# TinyCan.net
KiCad netlist of a schematic drawn in EAGLE
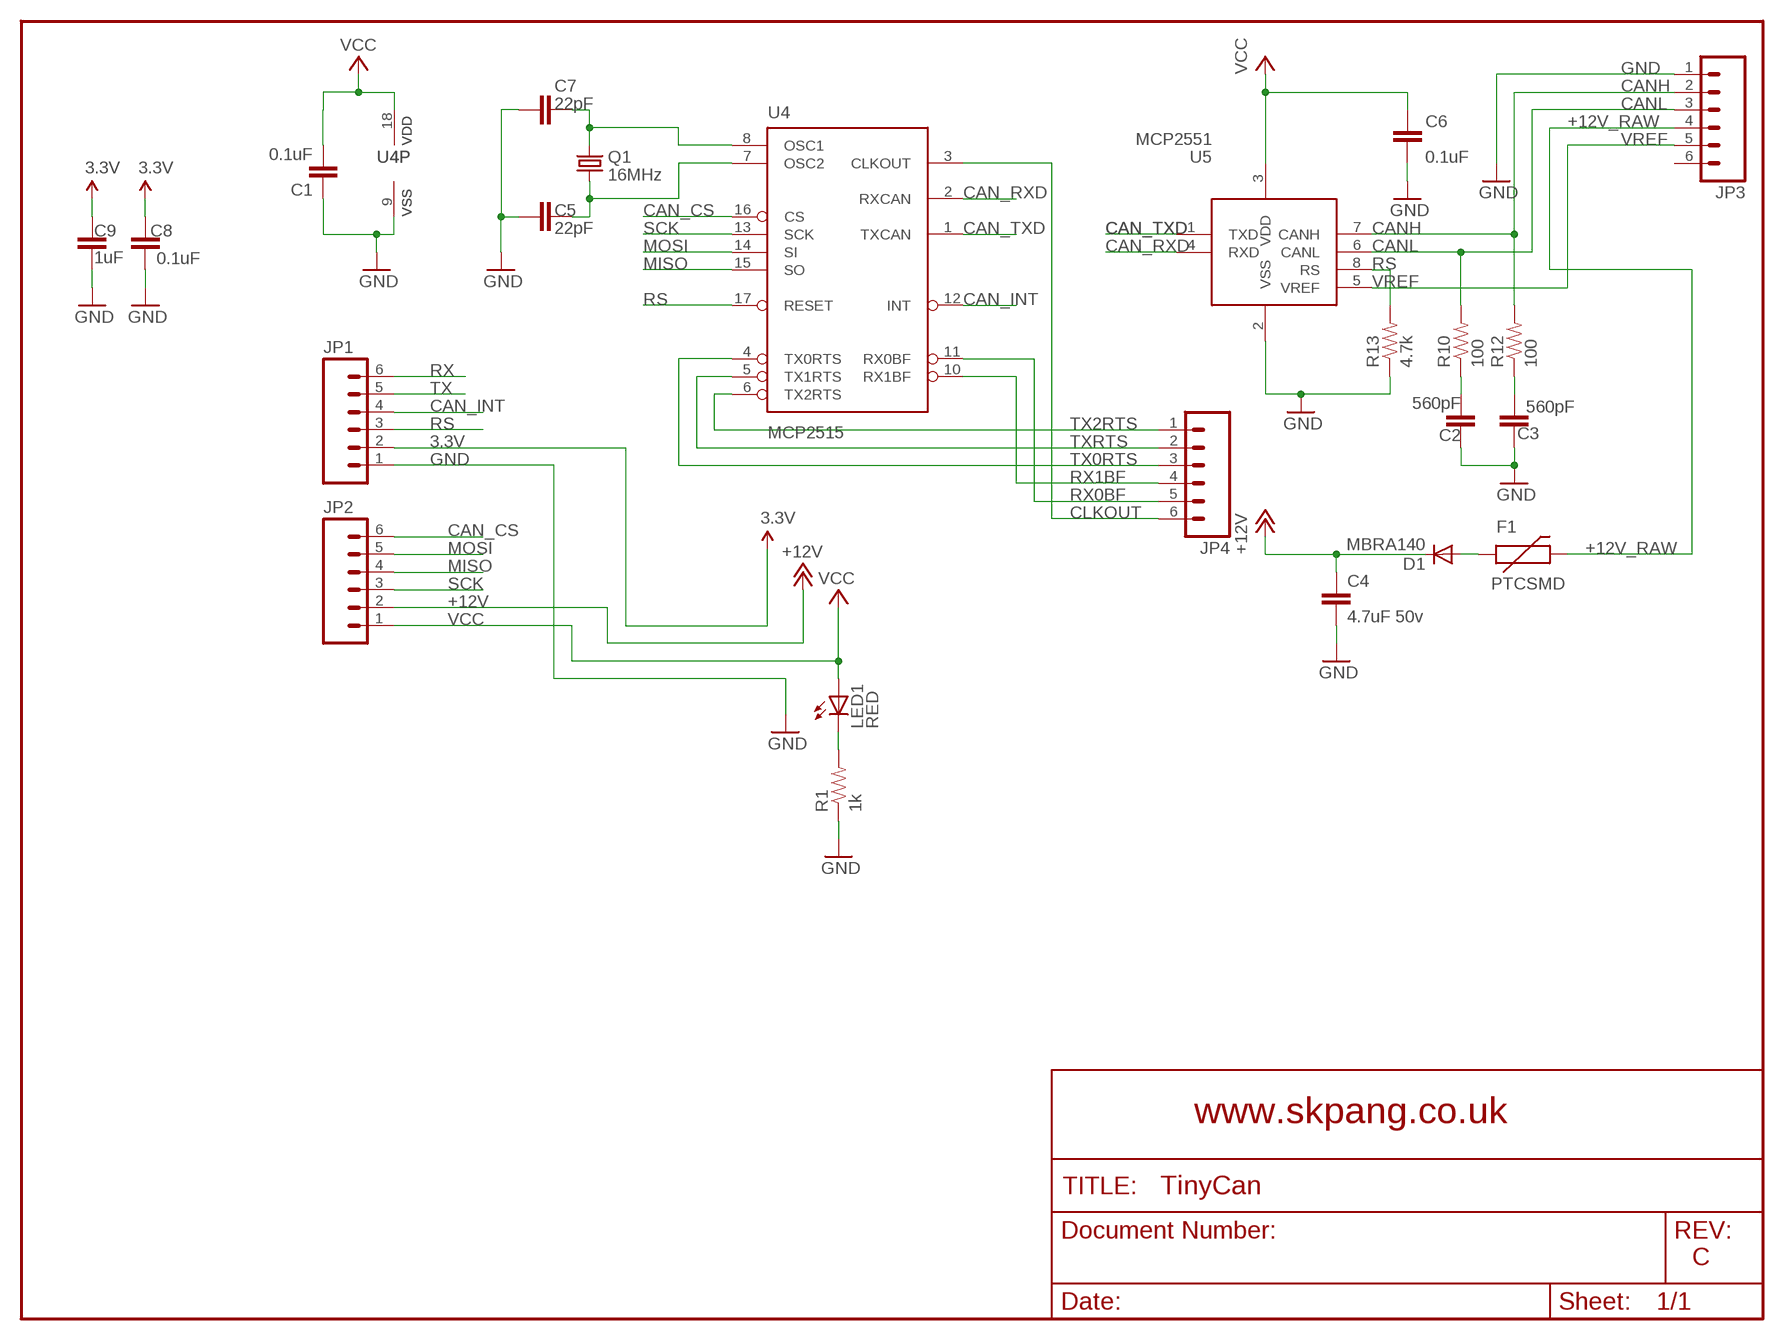
[diagram p0: schematic, sheet 1]

(export (version "E")
  (design (tool "Eeschema 10.0.6"))
  (components
    (comp (ref "C1")
      (value "0.1uF")
      (footprint "eagle-import:0603-CAP")
      (libsource (lib "eagle-import") (part "CAP0603-CAP"))
    )
    (comp (ref "C2")
      (value "560pF")
      (footprint "eagle-import:0603-CAP")
      (libsource (lib "eagle-import") (part "CAP0603-CAP"))
    )
    (comp (ref "C3")
      (value "560pF")
      (footprint "eagle-import:0603-CAP")
      (libsource (lib "eagle-import") (part "CAP0603-CAP"))
    )
    (comp (ref "C4")
      (value "4.7uF 50v")
      (footprint "eagle-import:0603-CAP")
      (libsource (lib "eagle-import") (part "CAP0603-CAP"))
    )
    (comp (ref "C5")
      (value "22pF")
      (footprint "eagle-import:0603-CAP")
      (libsource (lib "eagle-import") (part "CAP0603-CAP"))
    )
    (comp (ref "C6")
      (value "0.1uF")
      (footprint "eagle-import:0603-CAP")
      (libsource (lib "eagle-import") (part "CAP0603-CAP"))
    )
    (comp (ref "C7")
      (value "22pF")
      (footprint "eagle-import:0603-CAP")
      (libsource (lib "eagle-import") (part "CAP0603-CAP"))
    )
    (comp (ref "C8")
      (value "0.1uF")
      (footprint "eagle-import:0603-CAP")
      (libsource (lib "eagle-import") (part "CAP0603-CAP"))
    )
    (comp (ref "C9")
      (value "1uF")
      (footprint "eagle-import:0603-CAP")
      (libsource (lib "eagle-import") (part "CAP0603-CAP"))
    )
    (comp (ref "D1")
      (value "MBRA140")
      (footprint "eagle-import:SMA-DIODE")
      (libsource (lib "eagle-import") (part "DIODESMA"))
    )
    (comp (ref "F1")
      (value "PTCSMD")
      (footprint "eagle-import:PTC-1206")
      (libsource (lib "eagle-import") (part "PTCSMD"))
    )
    (comp (ref "JP1")
      (value "M06LOCK")
      (footprint "eagle-import:1X06_LOCK")
      (libsource (lib "eagle-import") (part "M06LOCK"))
    )
    (comp (ref "JP2")
      (value "M06LOCK")
      (footprint "eagle-import:1X06_LOCK")
      (libsource (lib "eagle-import") (part "M06LOCK"))
    )
    (comp (ref "JP3")
      (value "M06LOCK")
      (footprint "eagle-import:1X06_LOCK")
      (libsource (lib "eagle-import") (part "M06LOCK"))
    )
    (comp (ref "JP4")
      (value "M06LOCK")
      (footprint "eagle-import:1X06_LOCK")
      (libsource (lib "eagle-import") (part "M06LOCK"))
    )
    (comp (ref "LED1")
      (value "RED")
      (footprint "eagle-import:LED-0603")
      (libsource (lib "eagle-import") (part "LED0603"))
    )
    (comp (ref "Q1")
      (value "16MHz")
      (footprint "eagle-import:CRYSTAL-SMD-5X3")
      (libsource (lib "eagle-import") (part "CRYSTAL5X3"))
    )
    (comp (ref "R1")
      (value "1k")
      (footprint "eagle-import:0603-RES")
      (libsource (lib "eagle-import") (part "RESISTOR0603-RES"))
    )
    (comp (ref "R10")
      (value "100")
      (footprint "eagle-import:0603-RES")
      (libsource (lib "eagle-import") (part "RESISTOR0603-RES"))
    )
    (comp (ref "R12")
      (value "100")
      (footprint "eagle-import:0603-RES")
      (libsource (lib "eagle-import") (part "RESISTOR0603-RES"))
    )
    (comp (ref "R13")
      (value "4.7k")
      (footprint "eagle-import:0603-RES")
      (libsource (lib "eagle-import") (part "RESISTOR0603-RES"))
    )
    (comp (ref "U4")
      (value "MCP2515")
      (footprint "eagle-import:SO-18W")
      (libsource (lib "eagle-import") (part "MCP2510SO"))
    )
    (comp (ref "U5")
      (value "MCP2551")
      (footprint "eagle-import:SO-08M")
      (libsource (lib "eagle-import") (part "MCP2551"))
    )
  )
  (nets
    (net (code "1") (name "+12V") (class "Default")
      (node (ref "C4") (pin "1") (pinfunction "1_1") (pintype "passive"))
      (node (ref "D1") (pin "C") (pinfunction "C_C") (pintype "passive"))
      (node (ref "JP2") (pin "2") (pinfunction "2_2") (pintype "passive"))
    )
    (net (code "2") (name "/+12V_RAW") (class "Default")
      (node (ref "F1") (pin "2") (pinfunction "2_2") (pintype "bidirectional"))
      (node (ref "JP3") (pin "4") (pinfunction "4_4") (pintype "passive"))
    )
    (net (code "3") (name "/CANH") (class "Default")
      (node (ref "JP3") (pin "2") (pinfunction "2_2") (pintype "passive"))
      (node (ref "R12") (pin "2") (pinfunction "2_2") (pintype "passive"))
      (node (ref "U5") (pin "7") (pinfunction "CANH_7") (pintype "bidirectional"))
    )
    (net (code "4") (name "/CANL") (class "Default")
      (node (ref "JP3") (pin "3") (pinfunction "3_3") (pintype "passive"))
      (node (ref "R10") (pin "2") (pinfunction "2_2") (pintype "passive"))
      (node (ref "U5") (pin "6") (pinfunction "CANL_6") (pintype "bidirectional"))
    )
    (net (code "5") (name "/CAN_CS") (class "Default")
      (node (ref "JP2") (pin "6") (pinfunction "6_6") (pintype "passive"))
      (node (ref "U4") (pin "16") (pinfunction "CS_16") (pintype "input"))
    )
    (net (code "6") (name "/CAN_INT") (class "Default")
      (node (ref "JP1") (pin "4") (pinfunction "4_4") (pintype "passive"))
      (node (ref "U4") (pin "12") (pinfunction "INT_12") (pintype "output"))
    )
    (net (code "7") (name "/CAN_RXD") (class "Default")
      (node (ref "U4") (pin "2") (pinfunction "RXCAN_2") (pintype "input"))
      (node (ref "U5") (pin "4") (pinfunction "RXD_4") (pintype "bidirectional"))
    )
    (net (code "8") (name "/CAN_TXD") (class "Default")
      (node (ref "U4") (pin "1") (pinfunction "TXCAN_1") (pintype "output"))
      (node (ref "U5") (pin "1") (pinfunction "TXD_1") (pintype "bidirectional"))
    )
    (net (code "9") (name "/CLKOUT") (class "Default")
      (node (ref "JP4") (pin "6") (pinfunction "6_6") (pintype "passive"))
      (node (ref "U4") (pin "3") (pinfunction "CLKOUT_3") (pintype "output"))
    )
    (net (code "10") (name "/MISO") (class "Default")
      (node (ref "JP2") (pin "4") (pinfunction "4_4") (pintype "passive"))
      (node (ref "U4") (pin "15") (pinfunction "SO_15") (pintype "output"))
    )
    (net (code "11") (name "/MOSI") (class "Default")
      (node (ref "JP2") (pin "5") (pinfunction "5_5") (pintype "passive"))
      (node (ref "U4") (pin "14") (pinfunction "SI_14") (pintype "input"))
    )
    (net (code "12") (name "/RS") (class "Default")
      (node (ref "JP1") (pin "3") (pinfunction "3_3") (pintype "passive"))
      (node (ref "R13") (pin "2") (pinfunction "2_2") (pintype "passive"))
      (node (ref "U4") (pin "17") (pinfunction "RESET_17") (pintype "input"))
      (node (ref "U5") (pin "8") (pinfunction "RS_8") (pintype "bidirectional"))
    )
    (net (code "13") (name "/RX") (class "Default")
      (node (ref "JP1") (pin "6") (pinfunction "6_6") (pintype "passive"))
    )
    (net (code "14") (name "/RX0BF") (class "Default")
      (node (ref "JP4") (pin "5") (pinfunction "5_5") (pintype "passive"))
      (node (ref "U4") (pin "11") (pinfunction "RX0BF_11") (pintype "output"))
    )
    (net (code "15") (name "/RX1BF") (class "Default")
      (node (ref "JP4") (pin "4") (pinfunction "4_4") (pintype "passive"))
      (node (ref "U4") (pin "10") (pinfunction "RX1BF_10") (pintype "output"))
    )
    (net (code "16") (name "/SCK") (class "Default")
      (node (ref "JP2") (pin "3") (pinfunction "3_3") (pintype "passive"))
      (node (ref "U4") (pin "13") (pinfunction "SCK_13") (pintype "input"))
    )
    (net (code "17") (name "/TX") (class "Default")
      (node (ref "JP1") (pin "5") (pinfunction "5_5") (pintype "passive"))
    )
    (net (code "18") (name "/TX0RTS") (class "Default")
      (node (ref "JP4") (pin "3") (pinfunction "3_3") (pintype "passive"))
      (node (ref "U4") (pin "4") (pinfunction "TX0RTS_4") (pintype "input"))
    )
    (net (code "19") (name "/TX2RTS") (class "Default")
      (node (ref "JP4") (pin "1") (pinfunction "1_1") (pintype "passive"))
      (node (ref "U4") (pin "6") (pinfunction "TX2RTS_6") (pintype "input"))
    )
    (net (code "20") (name "/TXRTS") (class "Default")
      (node (ref "JP4") (pin "2") (pinfunction "2_2") (pintype "passive"))
      (node (ref "U4") (pin "5") (pinfunction "TX1RTS_5") (pintype "input"))
    )
    (net (code "21") (name "/VREF") (class "Default")
      (node (ref "JP3") (pin "5") (pinfunction "5_5") (pintype "passive"))
      (node (ref "U5") (pin "5") (pinfunction "VREF_5") (pintype "bidirectional"))
    )
    (net (code "22") (name "3.3V") (class "Default")
      (node (ref "C8") (pin "2") (pinfunction "2_2") (pintype "passive"))
      (node (ref "C9") (pin "1") (pinfunction "1_1") (pintype "passive"))
      (node (ref "JP1") (pin "2") (pinfunction "2_2") (pintype "passive"))
    )
    (net (code "23") (name "GND") (class "Default")
      (node (ref "C1") (pin "1") (pinfunction "1_1") (pintype "passive"))
      (node (ref "C2") (pin "1") (pinfunction "1_1") (pintype "passive"))
      (node (ref "C3") (pin "1") (pinfunction "1_1") (pintype "passive"))
      (node (ref "C4") (pin "2") (pinfunction "2_2") (pintype "passive"))
      (node (ref "C5") (pin "1") (pinfunction "1_1") (pintype "passive"))
      (node (ref "C6") (pin "1") (pinfunction "1_1") (pintype "passive"))
      (node (ref "C7") (pin "1") (pinfunction "1_1") (pintype "passive"))
      (node (ref "C8") (pin "1") (pinfunction "1_1") (pintype "passive"))
      (node (ref "C9") (pin "2") (pinfunction "2_2") (pintype "passive"))
      (node (ref "JP1") (pin "1") (pinfunction "1_1") (pintype "passive"))
      (node (ref "JP3") (pin "1") (pinfunction "1_1") (pintype "passive"))
      (node (ref "R1") (pin "1") (pinfunction "1_1") (pintype "passive"))
      (node (ref "R13") (pin "1") (pinfunction "1_1") (pintype "passive"))
      (node (ref "U4") (pin "9") (pinfunction "VSS_9") (pintype "power_in"))
      (node (ref "U5") (pin "2") (pinfunction "VSS_2") (pintype "power_in"))
    )
    (net (code "24") (name "Net-(C2-Pad2)") (class "Default")
      (node (ref "C2") (pin "2") (pinfunction "2_2") (pintype "passive"))
      (node (ref "R10") (pin "1") (pinfunction "1_1") (pintype "passive"))
    )
    (net (code "25") (name "Net-(C3-Pad2)") (class "Default")
      (node (ref "C3") (pin "2") (pinfunction "2_2") (pintype "passive"))
      (node (ref "R12") (pin "1") (pinfunction "1_1") (pintype "passive"))
    )
    (net (code "26") (name "Net-(D1-PadA)") (class "Default")
      (node (ref "D1") (pin "A") (pinfunction "A_A") (pintype "passive"))
      (node (ref "F1") (pin "1") (pinfunction "1_1") (pintype "bidirectional"))
    )
    (net (code "27") (name "Net-(LED1-PadC)") (class "Default")
      (node (ref "LED1") (pin "C") (pinfunction "C_C") (pintype "passive"))
      (node (ref "R1") (pin "2") (pinfunction "2_2") (pintype "passive"))
    )
    (net (code "28") (name "Net-(Q1-2)") (class "Default")
      (node (ref "C7") (pin "2") (pinfunction "2_2") (pintype "passive"))
      (node (ref "Q1") (pin "3") (pinfunction "2_3") (pintype "passive"))
      (node (ref "U4") (pin "8") (pinfunction "OSC1_8") (pintype "input"))
    )
    (net (code "29") (name "Net-(U4A-OSC2)") (class "Default")
      (node (ref "C5") (pin "2") (pinfunction "2_2") (pintype "passive"))
      (node (ref "Q1") (pin "1") (pinfunction "1_1") (pintype "passive"))
      (node (ref "U4") (pin "7") (pinfunction "OSC2_7") (pintype "output"))
    )
    (net (code "30") (name "VCC") (class "Default")
      (node (ref "C1") (pin "2") (pinfunction "2_2") (pintype "passive"))
      (node (ref "C6") (pin "2") (pinfunction "2_2") (pintype "passive"))
      (node (ref "JP2") (pin "1") (pinfunction "1_1") (pintype "passive"))
      (node (ref "LED1") (pin "A") (pinfunction "A_A") (pintype "passive"))
      (node (ref "U4") (pin "18") (pinfunction "VDD_18") (pintype "power_in"))
      (node (ref "U5") (pin "3") (pinfunction "VDD_3") (pintype "power_in"))
    )
    (net (code "31") (name "unconnected-(JP3-Pad6)") (class "Default")
      (node (ref "JP3") (pin "6") (pinfunction "6_6") (pintype "passive"))
    )
  )
)
